# microcontroller.net
KiCad netlist of a schematic drawn in Altium Designer
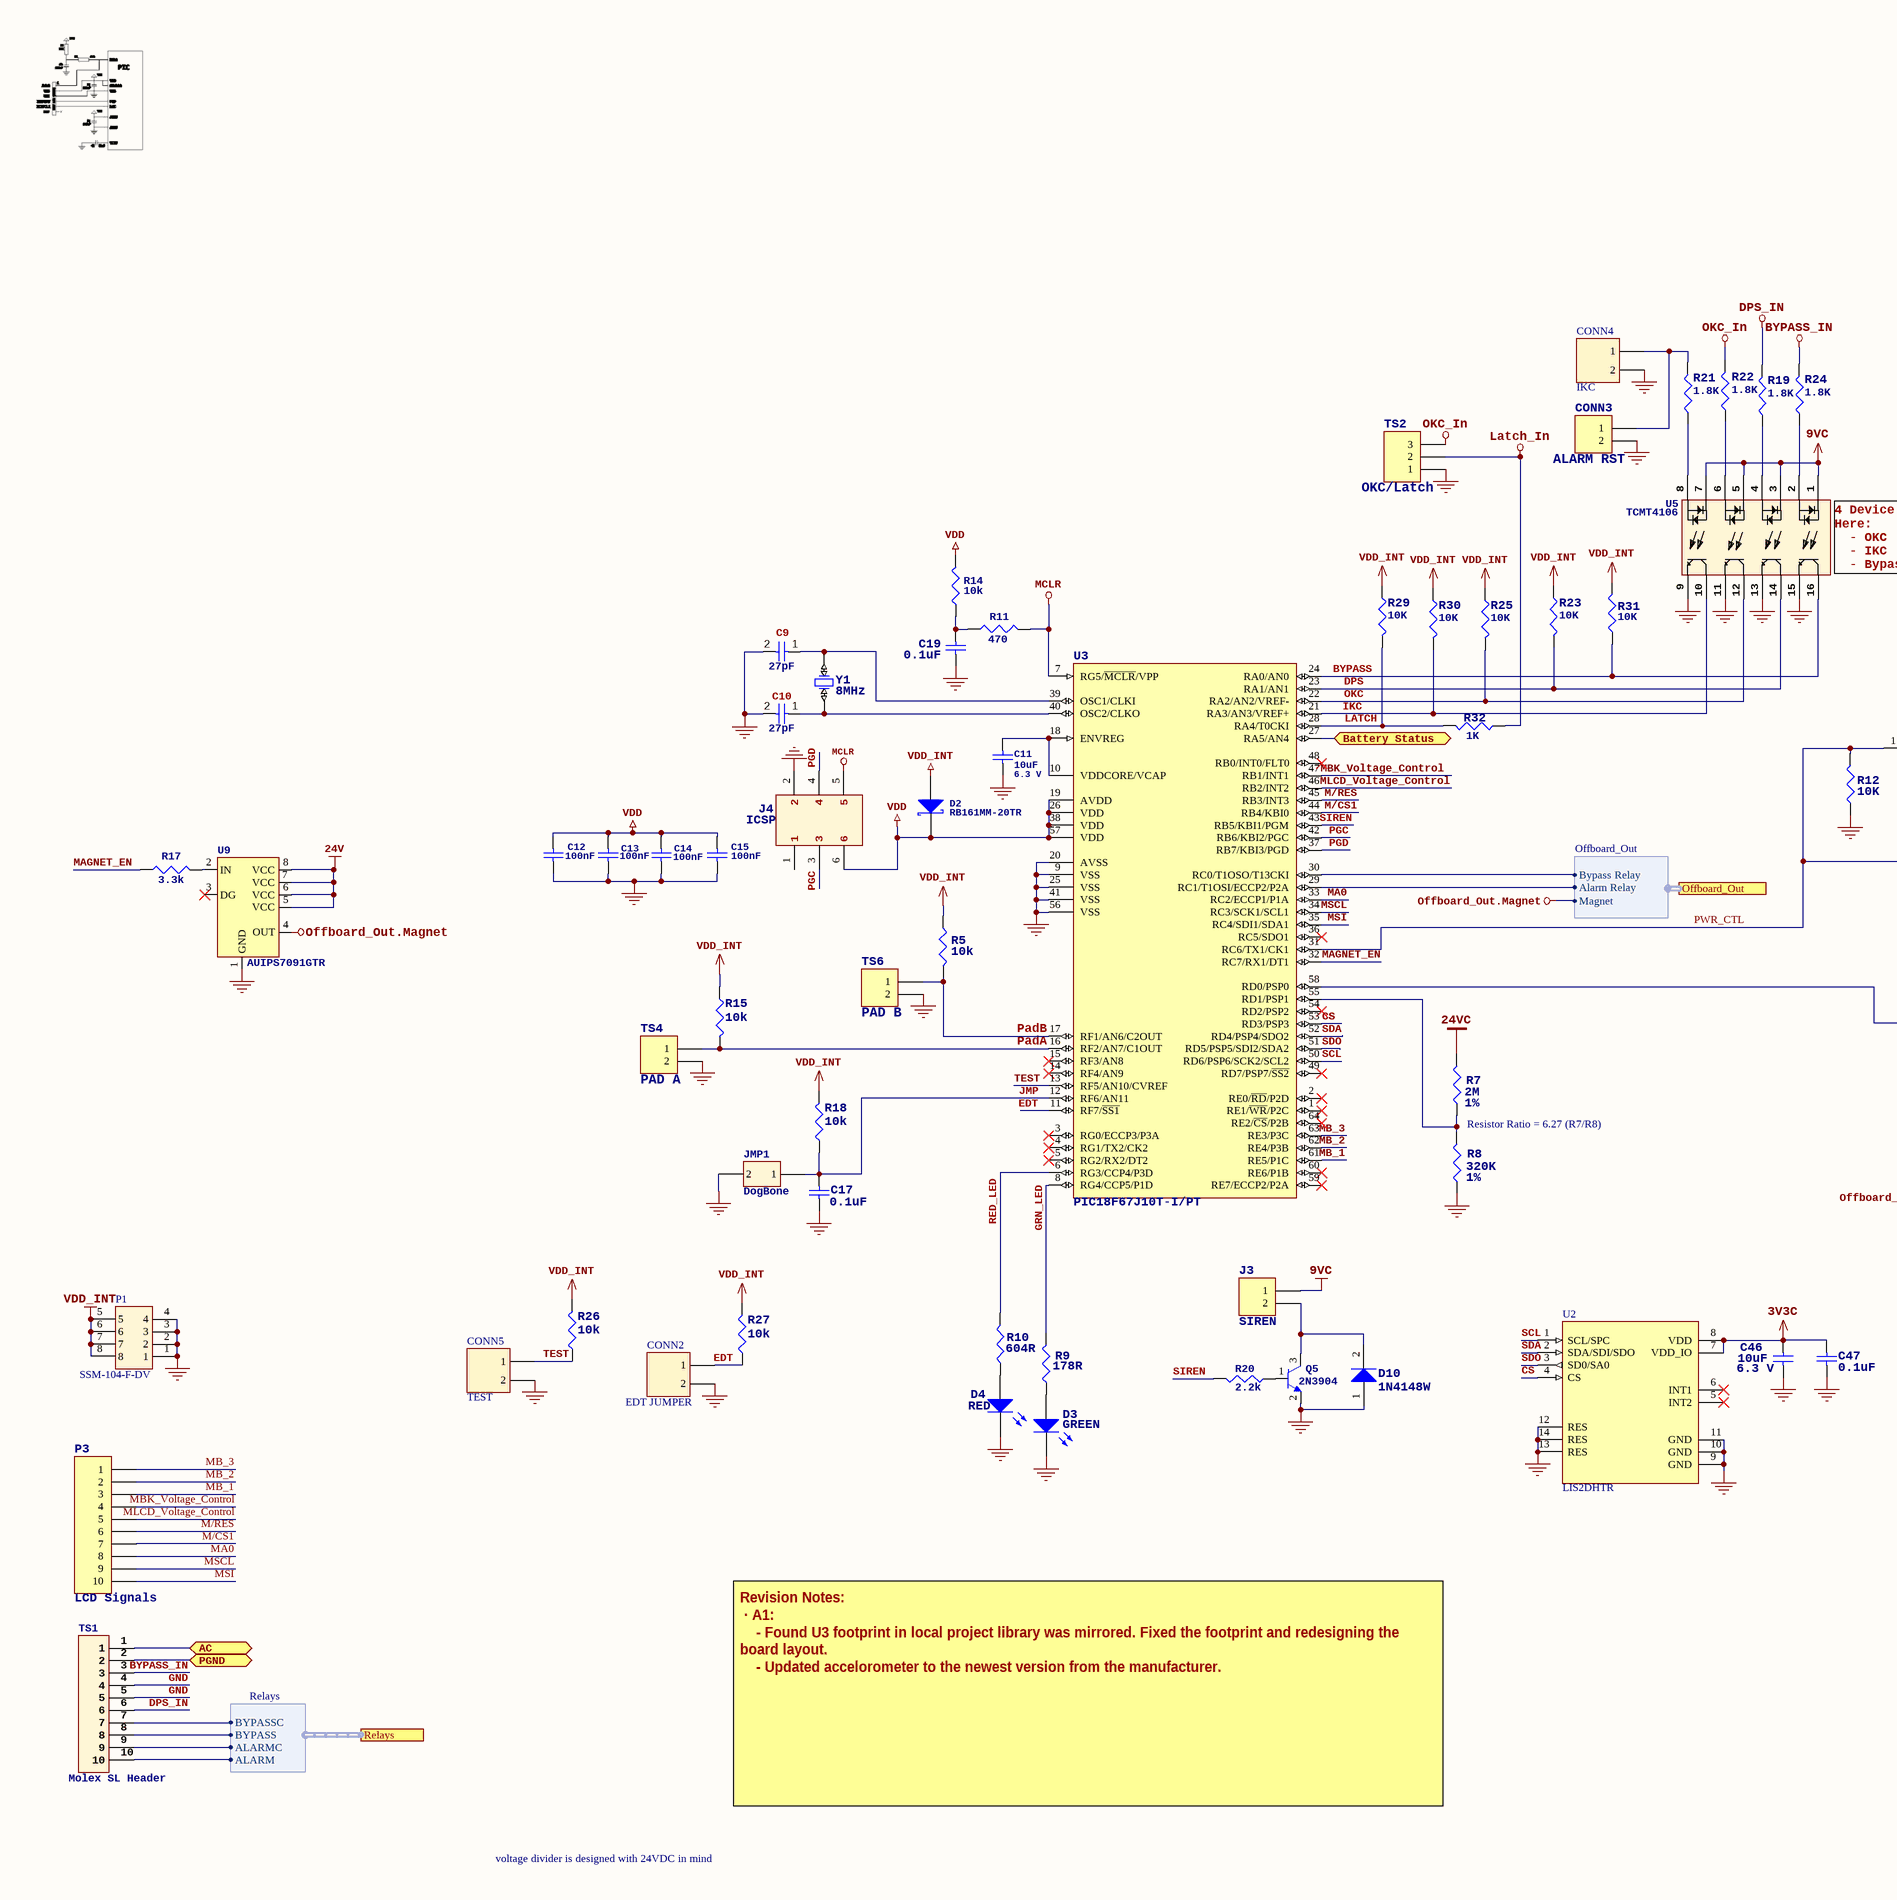
[diagram p0: microcontroller.SchDoc, left]
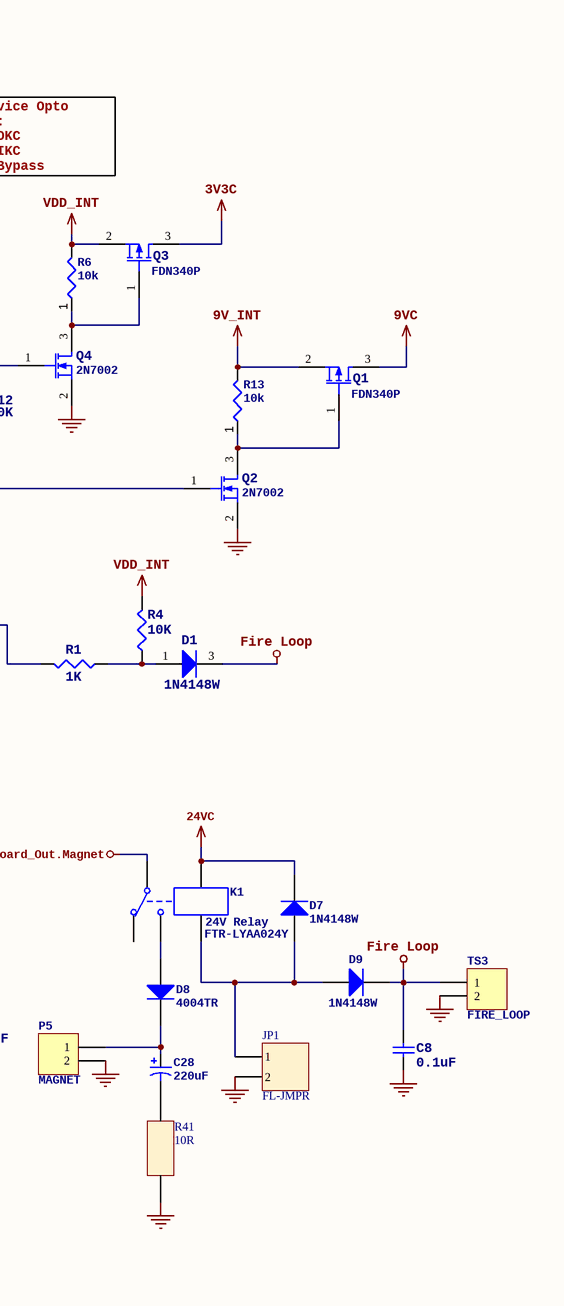
[diagram p1: microcontroller.SchDoc, right]

(export (version "E")
  (design (tool "Eeschema 10.0.6"))
  (components
    (comp (ref "C8")
      (value "0.1uF")
      (footprint "C0805")
      (description "Capacitor Ceramic X7R 50V 0.1uF 0805 SMT")
      (fields (field (name "MFR") "KEMET") (field (name "Comment") "Cap"))
      (libsource (lib "Miscellaneous Devices") (part "Cap"))
    )
    (comp (ref "C9")
      (value "27pF")
      (footprint "C0805")
      (description "Multilayer Ceramic Capacitors MLCC - SMD/SMT 100V 27pF C0G 0805 5% AEC-Q200")
      (fields (field (name "TOLERANCE") "20%") (field (name "MFR") "AVX"))
      (libsource (lib "Altium Concord Pro on Altium 365") (part "CAP-NP-2"))
    )
    (comp (ref "C10")
      (value "27pF")
      (footprint "C0805")
      (description "Multilayer Ceramic Capacitors MLCC - SMD/SMT 100V 27pF C0G 0805 5% AEC-Q200")
      (fields (field (name "TOLERANCE") "20%") (field (name "MFR") "AVX"))
      (libsource (lib "Altium Concord Pro on Altium 365") (part "CAP-NP-2"))
    )
    (comp (ref "C11")
      (value "10uF")
      (footprint "C0805")
      (description "Multilayer Ceramic Capacitors MLCC - SMD/SMT CGA 0805 6.3V 10uF X7R 10% AEC-Q200")
      (fields (field (name "MFR") "TDK") (field (name "VOLTAGE") "6.3 V") (field (name "Comment") "Cap"))
      (libsource (lib "Miscellaneous Devices") (part "Cap"))
    )
    (comp (ref "C12")
      (value "100nF")
      (footprint "C0805")
      (description "Capacitor")
      (fields (field (name "Comment") "Cap"))
      (libsource (lib "Miscellaneous Devices") (part "Cap"))
    )
    (comp (ref "C13")
      (value "100nF")
      (footprint "C0805")
      (description "Capacitor")
      (fields (field (name "Comment") "Cap"))
      (libsource (lib "Miscellaneous Devices") (part "Cap"))
    )
    (comp (ref "C14")
      (value "100nF")
      (footprint "C0805")
      (description "Capacitor")
      (fields (field (name "Comment") "Cap"))
      (libsource (lib "Miscellaneous Devices") (part "Cap"))
    )
    (comp (ref "C15")
      (value "100nF")
      (footprint "C0805")
      (description "Capacitor")
      (fields (field (name "Comment") "Cap"))
      (libsource (lib "Miscellaneous Devices") (part "Cap"))
    )
    (comp (ref "C17")
      (value "0.1uF")
      (footprint "C0805")
      (description "Capacitor Ceramic X7R 50V 0.1uF 0805 SMT")
      (fields (field (name "MFR") "KEMET") (field (name "Comment") "Cap"))
      (libsource (lib "Miscellaneous Devices") (part "Cap"))
    )
    (comp (ref "C19")
      (value "0.1uF")
      (footprint "C0805")
      (description "Capacitor Ceramic X7R 50V 0.1uF 0805 SMT")
      (fields (field (name "MFR") "KEMET") (field (name "Comment") "Cap"))
      (libsource (lib "Miscellaneous Devices") (part "Cap"))
    )
    (comp (ref "C28")
      (value "220uF")
      (footprint "10x12.5 CAP")
      (description "Polarized Capacitor (Surface Mount)")
      (fields (field (name "MFR") "Nichicon") (field (name "Comment") "Cap Pol3"))
      (libsource (lib "Miscellaneous Devices") (part "Cap Pol3"))
    )
    (comp (ref "C46")
      (value "10uF")
      (footprint "C0805")
      (description "Multilayer Ceramic Capacitors MLCC - SMD/SMT CGA 0805 6.3V 10uF X7R 10% AEC-Q200")
      (fields (field (name "MFR") "TDK") (field (name "VOLTAGE") "6.3 V") (field (name "Comment") "Cap"))
      (libsource (lib "Miscellaneous Devices") (part "Cap"))
    )
    (comp (ref "C47")
      (value "0.1uF")
      (footprint "C0805")
      (description "Capacitor Ceramic X7R 50V 0.1uF 0805 SMT")
      (fields (field (name "MFR") "KEMET") (field (name "Comment") "Cap"))
      (libsource (lib "Miscellaneous Devices") (part "Cap"))
    )
    (comp (ref "CONN2")
      (value "EDT JUMPER")
      (footprint "2 Pin Header")
      (description "2.54mm Pitch 2 Way 1 Row Straight Pin Header, Through Hole")
      (fields (field (name "MFR") "TE Connectivity"))
      (libsource (lib "Custom Components") (part "Header 2"))
    )
    (comp (ref "CONN3")
      (value "ALARM RST")
      (footprint "BAT-2")
      (description "Header, 2-Pin")
      (libsource (lib "Miscellaneous Connectors") (part "Header 2"))
    )
    (comp (ref "CONN4")
      (value "IKC")
      (footprint "2 Pin Header")
      (description "2.54mm Pitch 2 Way 1 Row Straight Pin Header, Through Hole")
      (fields (field (name "MFR") "TE Connectivity"))
      (libsource (lib "Custom Components") (part "Header 2"))
    )
    (comp (ref "CONN5")
      (value "TEST")
      (footprint "2 Pin Header")
      (description "2.54mm Pitch 2 Way 1 Row Straight Pin Header, Through Hole")
      (fields (field (name "MFR") "TE Connectivity"))
      (libsource (lib "Custom Components") (part "Header 2"))
    )
    (comp (ref "D1")
      (value "Diode")
      (footprint "SOT-23_M")
      (description "DIODE SIGNAL SMT 75 VOLTS")
      (fields (field (name "MFR P/N") "1N4148W"))
      (libsource (lib "") (part "Diode_2"))
    )
    (comp (ref "D2")
      (value "D Schottky")
      (footprint "SOD-123FL")
      (description "Schottky Barrier Rectifier")
      (fields (field (name "MFR") "ROHM Semiconductor") (field (name "MFR P/N") "RB161MM-20TR"))
      (libsource (lib "Custom Components") (part "D Schottky"))
    )
    (comp (ref "D3")
      (value "GREEN")
      (footprint "T-1 3/4")
      (description "Typical RED, GREEN, YELLOW, AMBER GaAs LED")
      (fields (field (name "MFR") "Kingbright"))
      (libsource (lib "Miscellaneous Devices") (part "LED2"))
    )
    (comp (ref "D4")
      (value "RED")
      (footprint "T-1 3/4")
      (description "Typical RED, GREEN, YELLOW, AMBER GaAs LED")
      (fields (field (name "MFR") "Kingbright"))
      (libsource (lib "Miscellaneous Devices") (part "LED2"))
    )
    (comp (ref "D7")
      (value "Diode")
      (footprint "SOT-23_M")
      (description "DIODE SIGNAL SMT 75 VOLTS")
      (fields (field (name "MFR P/N") "1N4148W"))
      (libsource (lib "Miscellaneous Devices") (part "Diode"))
    )
    (comp (ref "D8")
      (value "Diode")
      (footprint "SMB")
      (description "DIODE RECTIFIER 4004 SMT")
      (fields (field (name "MFR P/N") "4004TR"))
      (libsource (lib "Miscellaneous Devices") (part "Diode"))
    )
    (comp (ref "D9")
      (value "Diode")
      (footprint "SOT-23_M")
      (description "DIODE SIGNAL SMT 75 VOLTS")
      (fields (field (name "MFR P/N") "1N4148W"))
      (libsource (lib "") (part "Diode_3"))
    )
    (comp (ref "D10")
      (value "Diode")
      (footprint "SOT-23_M")
      (description "DIODE SIGNAL SMT 75 VOLTS")
      (fields (field (name "MFR P/N") "1N4148W"))
      (libsource (lib "") (part "Diode_1"))
    )
    (comp (ref "J3")
      (value "SIREN")
      (footprint "BAT-2")
      (description "Header, 2-Pin")
      (libsource (lib "Miscellaneous Connectors") (part "Header 2"))
    )
    (comp (ref "J4")
      (value "ICSP")
      (footprint "ICSP SMT")
      (description "ICSP Header, 6-Pin, 2 Row")
      (libsource (lib "Custom Components") (part "ICSP_PIC"))
    )
    (comp (ref "JMP1")
      (value "DogBone")
      (footprint "DogBone")
      (libsource (lib "Custom Components") (part "DogBone"))
    )
    (comp (ref "JP1")
      (value "FL-JMPR")
      (footprint "2 Pin Header")
      (description "2.54mm Pitch 2 Way 1 Row Straight Pin Header, Through Hole")
      (fields (field (name "MFR") "TE Connectivity"))
      (libsource (lib "") (part "Header 2_1"))
    )
    (comp (ref "K1")
      (value "24V Relay")
      (footprint "FTR-LY")
      (description "SPST (1 Form A)")
      (fields (field (name "MFR") "Fujitsu") (field (name "MFR P/N") "FTR-LYAA024Y"))
      (libsource (lib "Miscellaneous Devices") (part "Relay-SPDT"))
    )
    (comp (ref "P1")
      (value "LCD Power")
      (footprint "MOLEX 15453508")
      (fields (field (name "MFR") "Samtec") (field (name "MFR P/N") "SSM-104-F-DV"))
      (libsource (lib "Custom Components") (part "2x4 Header"))
    )
    (comp (ref "P3")
      (value "LCD Signals")
      (footprint "10 pin Header")
      (description "Headers & Wire Housings 10 PIN SIL VERTICAL SOCKET")
      (fields (field (name "MFR") "Harwin"))
      (libsource (lib "Custom Components") (part "Header 10"))
    )
    (comp (ref "P5")
      (value "MAGNET")
      (footprint "7025")
      (description "Header, 2-Pin")
      (fields (field (name "MFR") "Molex"))
      (libsource (lib "Miscellaneous Connectors") (part "Header 2"))
    )
    (comp (ref "Q1")
      (value "FDN340P")
      (footprint "SOT-23_N")
      (description "P-Channel MOSFET")
      (fields (field (name "MFR") "ON Semiconductor / Fairchild"))
      (libsource (lib "Miscellaneous Devices") (part "MOSFET-P"))
    )
    (comp (ref "Q2")
      (value "2N7002")
      (footprint "SOT-23_N")
      (description "N-Channel MOSFET")
      (fields (field (name "MFR") "ON Semiconductor"))
      (libsource (lib "Miscellaneous Devices") (part "MOSFET-N"))
    )
    (comp (ref "Q3")
      (value "FDN340P")
      (footprint "SOT-23_N")
      (description "P-Channel MOSFET")
      (fields (field (name "MFR") "ON Semiconductor / Fairchild"))
      (libsource (lib "Miscellaneous Devices") (part "MOSFET-P"))
    )
    (comp (ref "Q4")
      (value "2N7002")
      (footprint "SOT-23_N")
      (description "N-Channel MOSFET")
      (fields (field (name "MFR") "ON Semiconductor"))
      (libsource (lib "Miscellaneous Devices") (part "MOSFET-N"))
    )
    (comp (ref "Q5")
      (value "2N3904")
      (footprint "SOT-23_N")
      (description "NPN Darlington Bipolar Transistor")
      (libsource (lib "Miscellaneous Devices") (part "2N3904_SMT"))
    )
    (comp (ref "R1")
      (value "1K")
      (footprint "6-0805_N")
      (description "Resistor 1K Ohm 1% 0805 SMT")
      (fields (field (name "MFR") "Vishay/Dale") (field (name "Comment") "Res3"))
      (libsource (lib "Miscellaneous Devices") (part "Res3"))
    )
    (comp (ref "R4")
      (value "10K")
      (footprint "6-0805_N")
      (description "Resistor")
      (fields (field (name "Comment") "Res3"))
      (libsource (lib "Miscellaneous Devices") (part "Res3"))
    )
    (comp (ref "R5")
      (value "10k")
      (footprint "6-0805_N")
      (description "Resistor")
      (fields (field (name "Comment") "Res3"))
      (libsource (lib "Miscellaneous Devices") (part "Res3"))
    )
    (comp (ref "R6")
      (value "10k")
      (footprint "6-0805_N")
      (description "Chip Resistor, 10 KOhm, +/- 1%, 01 W, -55 to 155 degC, 0805")
      (fields (field (name "TOLERANCE") "1%") (field (name "POWER") "100mW"))
      (libsource (lib "Altium Concord Pro on Altium 365") (part "RES-2"))
    )
    (comp (ref "R7")
      (value "1%")
      (footprint "6-0805_N")
      (description "Resistor 2M Ohm 1% 0805 SMT")
      (fields (field (name "ALTIUM_VALUE") "2M") (field (name "MFR") "Vishay/Dale"))
      (libsource (lib "Miscellaneous Devices") (part "Res3"))
    )
    (comp (ref "R8")
      (value "1%")
      (footprint "6-0805_N")
      (description "Thin Film Resistors - SMD 1/8W 316K ohm 1% 50ppm")
      (fields (field (name "ALTIUM_VALUE") "320K") (field (name "MFR") "Yageo"))
      (libsource (lib "Miscellaneous Devices") (part "Res3"))
    )
    (comp (ref "R9")
      (value "178R")
      (footprint "6-0805_N")
      (description "Resistor")
      (fields (field (name "MFR") "Vishay / Dale") (field (name "Comment") "Res3"))
      (libsource (lib "Miscellaneous Devices") (part "Res3"))
    )
    (comp (ref "R10")
      (value "604R")
      (footprint "6-0805_N")
      (description "Thick Film Resistors - SMD 1/8Watt 604ohms 1%")
      (fields (field (name "MFR") "Vishay / Dale") (field (name "Comment") "Res3"))
      (libsource (lib "Miscellaneous Devices") (part "Res3"))
    )
    (comp (ref "R11")
      (value "470")
      (footprint "6-0805_N")
      (description "Chip Resistor, 1 KOhm, +/-1%, 0.1 W, -55 to 155 degC, 0603 (1608 Metric)")
      (fields (field (name "POWER") "100mW") (field (name "TOLERANCE") "1%"))
      (libsource (lib "") (part "RES-2_1"))
    )
    (comp (ref "R12")
      (value "10K")
      (footprint "6-0805_N")
      (description "Resistor")
      (fields (field (name "Comment") "Res3"))
      (libsource (lib "Miscellaneous Devices") (part "Res3"))
    )
    (comp (ref "R13")
      (value "10k")
      (footprint "6-0805_N")
      (description "Chip Resistor, 10 KOhm, +/- 1%, 01 W, -55 to 155 degC, 0805")
      (fields (field (name "TOLERANCE") "1%") (field (name "POWER") "100mW"))
      (libsource (lib "Altium Concord Pro on Altium 365") (part "RES-2"))
    )
    (comp (ref "R14")
      (value "10k")
      (footprint "6-0805_N")
      (description "Chip Resistor, 10 KOhm, +/- 1%, 01 W, -55 to 155 degC, 0805")
      (fields (field (name "TOLERANCE") "1%") (field (name "POWER") "100mW"))
      (libsource (lib "") (part "RES-2_1"))
    )
    (comp (ref "R15")
      (value "10k")
      (footprint "6-0805_N")
      (description "Resistor")
      (fields (field (name "Comment") "Res3"))
      (libsource (lib "Miscellaneous Devices") (part "Res3"))
    )
    (comp (ref "R17")
      (value "3.3k")
      (footprint "6-0805_N")
      (description "Resistor 3.3KOhm 5% 0805 SMT")
      (fields (field (name "MFR") "Vishay/Dale") (field (name "Comment") "Res3"))
      (libsource (lib "Miscellaneous Devices") (part "Res3"))
    )
    (comp (ref "R18")
      (value "10k")
      (footprint "6-0805_N")
      (description "Resistor")
      (fields (field (name "Comment") "Res3"))
      (libsource (lib "Miscellaneous Devices") (part "Res3"))
    )
    (comp (ref "R19")
      (value "1.8K")
      (footprint "6-0805_N")
      (description "Resistor")
      (fields (field (name "MFR") "Vishay / Dale") (field (name "Comment") "Res3"))
      (libsource (lib "Miscellaneous Devices") (part "Res3"))
    )
    (comp (ref "R20")
      (value "2.2k")
      (footprint "6-0805_N")
      (description "Chip Resistor, 2.2KOhm, +/- 5%, 01 W, -55 to 155 degC, 0805")
      (fields (field (name "TOLERANCE") "1%") (field (name "POWER") "100mW"))
      (libsource (lib "") (part "RES-2_1"))
    )
    (comp (ref "R21")
      (value "1.8K")
      (footprint "6-0805_N")
      (description "Resistor")
      (fields (field (name "MFR") "Vishay / Dale") (field (name "Comment") "Res3"))
      (libsource (lib "Miscellaneous Devices") (part "Res3"))
    )
    (comp (ref "R22")
      (value "1.8K")
      (footprint "6-0805_N")
      (description "Resistor")
      (fields (field (name "MFR") "Vishay / Dale") (field (name "Comment") "Res3"))
      (libsource (lib "Miscellaneous Devices") (part "Res3"))
    )
    (comp (ref "R23")
      (value "10K")
      (footprint "6-0805_N")
      (description "Resistor")
      (fields (field (name "Comment") "Res3"))
      (libsource (lib "Miscellaneous Devices") (part "Res3"))
    )
    (comp (ref "R24")
      (value "1.8K")
      (footprint "6-0805_N")
      (description "Resistor")
      (fields (field (name "MFR") "Vishay / Dale") (field (name "Comment") "Res3"))
      (libsource (lib "Miscellaneous Devices") (part "Res3"))
    )
    (comp (ref "R25")
      (value "10K")
      (footprint "6-0805_N")
      (description "Resistor")
      (fields (field (name "Comment") "Res3"))
      (libsource (lib "Miscellaneous Devices") (part "Res3"))
    )
    (comp (ref "R26")
      (value "10k")
      (footprint "6-0805_N")
      (description "Resistor")
      (fields (field (name "Comment") "Res3"))
      (libsource (lib "Miscellaneous Devices") (part "Res3"))
    )
    (comp (ref "R27")
      (value "10k")
      (footprint "6-0805_N")
      (description "Resistor")
      (fields (field (name "Comment") "Res3"))
      (libsource (lib "Miscellaneous Devices") (part "Res3"))
    )
    (comp (ref "R29")
      (value "10K")
      (footprint "6-0805_N")
      (description "Resistor")
      (fields (field (name "Comment") "Res3"))
      (libsource (lib "Miscellaneous Devices") (part "Res3"))
    )
    (comp (ref "R30")
      (value "10K")
      (footprint "6-0805_N")
      (description "Resistor")
      (fields (field (name "Comment") "Res3"))
      (libsource (lib "Miscellaneous Devices") (part "Res3"))
    )
    (comp (ref "R31")
      (value "10K")
      (footprint "6-0805_N")
      (description "Resistor")
      (fields (field (name "Comment") "Res3"))
      (libsource (lib "Miscellaneous Devices") (part "Res3"))
    )
    (comp (ref "R32")
      (value "1K")
      (footprint "6-0805_N")
      (description "Resistor 1K Ohm 1% 0805 SMT")
      (fields (field (name "MFR") "Vishay/Dale") (field (name "Comment") "Res3"))
      (libsource (lib "Miscellaneous Devices") (part "Res3"))
    )
    (comp (ref "R41")
      (value "10R")
      (footprint "RESC_1210")
      (description "Resistor 10 Ohm 5% 1210 SMD")
      (fields (field (name "MFR") "Vishay/Dale"))
      (libsource (lib "Custom Components") (part "RESC_1210"))
    )
    (comp (ref "TS1")
      (value "Molex SL Header")
      (footprint "10 Pin Molex Horizontal - duplicate")
      (fields (field (name "MFR") "Molex"))
      (libsource (lib "Custom Components") (part "SPOX-10P"))
    )
    (comp (ref "TS2")
      (value "OKC/Latch")
      (footprint "3 Pin Footprint")
      (description "Header, 3-Pin, Right Angle")
      (fields (field (name "MFR") "Molex"))
      (libsource (lib "Miscellaneous Connectors") (part "Header 3H"))
    )
    (comp (ref "TS3")
      (value "FIRE_LOOP")
      (footprint "BAT-2")
      (description "Header, 2-Pin, Right Angle")
      (libsource (lib "") (part "Header 2H_1"))
    )
    (comp (ref "TS4")
      (value "PAD A")
      (footprint "BAT-2")
      (description "Header, 2-Pin, Right Angle")
      (libsource (lib "Miscellaneous Connectors") (part "Header 2H"))
    )
    (comp (ref "TS6")
      (value "PAD B")
      (footprint "BAT-2")
      (description "Header, 2-Pin")
      (fields (field (name "MFR") "Molex"))
      (libsource (lib "Miscellaneous Connectors") (part "Header 2"))
    )
    (comp (ref "U2")
      (value "LIS2DHTR")
      (footprint "PQFN35P200X200X100-14N")
      (description "Accelerometer X, Y, Z Axis Â±2g, 4g, 8g, 16g 0.5Hz ~ 672Hz 14-LGA _2x2_")
      (fields (field (name "MF") "STMicroelectronics"))
      (libsource (lib "Custom Components") (part "LIS2DHTR"))
    )
    (comp (ref "U3")
      (value "PIC18F67J10T-I/PT")
      (footprint "PIC18F67J10T-I/PT")
      (fields (field (name "MFR") "Microchip"))
      (libsource (lib "Custom Components") (part "CMP-0116-00693-1"))
    )
    (comp (ref "U5")
      (value "TCMT4106")
      (footprint "SSOP-16")
      (description "Transistor Output Optocouplers Phototransistor Out Quad CTR > 160-320%")
      (fields (field (name "MFR") "Vishay Semiconductors"))
      (libsource (lib "Custom Components") (part "ILQ615-4X009"))
    )
    (comp (ref "U9")
      (value "AUIPS7091GTR")
      (footprint "SOIC127P600X175-8N")
      (description "High Side MOSFET Switcher")
      (fields (field (name "MFR") "International Rectifier/Infineon"))
      (libsource (lib "Custom Components") (part "AUIPS7091GTR"))
    )
    (comp (ref "Y1")
      (value "8MHz")
      (footprint "ABM3")
      (description "Crystal Oscillator 8MHz")
      (fields (field (name "MFR") "Abracom"))
      (libsource (lib "Miscellaneous Devices") (part "XTAL"))
    )
  )
  (nets
    (net (code "3") (name "/AC") (class "Default")
      (node (ref "TS1") (pin "1") (pinfunction "1_1") (pintype "passive"))
    )
    (net (code "4") (name "/ALARM") (class "Default")
      (node (ref "TS1") (pin "10") (pinfunction "10_10") (pintype "passive"))
    )
    (net (code "5") (name "/ALARMC") (class "Default")
      (node (ref "TS1") (pin "9") (pinfunction "9_9") (pintype "passive"))
    )
    (net (code "6") (name "/Alarm Relay") (class "Default")
      (node (ref "U3") (pin "29") (pinfunction "RC1/T1OSI/ECCP2/P2A_29") (pintype "bidirectional"))
    )
    (net (code "7") (name "/BYPASS") (class "Default")
      (node (ref "R31") (pin "1") (pinfunction "1_1") (pintype "passive"))
      (node (ref "U3") (pin "24") (pinfunction "RA0/AN0_24") (pintype "bidirectional"))
      (node (ref "U5") (pin "16") (pinfunction "16_16") (pintype "passive"))
    )
    (net (code "8") (name "/BYPASSC") (class "Default")
      (node (ref "TS1") (pin "7") (pinfunction "7_7") (pintype "passive"))
    )
    (net (code "9") (name "/Battery Status") (class "Default")
      (node (ref "U3") (pin "27") (pinfunction "RA5/AN4_27") (pintype "bidirectional"))
    )
    (net (code "10") (name "/Bypass Relay") (class "Default")
      (node (ref "U3") (pin "30") (pinfunction "RC0/T1OSO/T13CKI_30") (pintype "bidirectional"))
    )
    (net (code "11") (name "/CS") (class "Default")
      (node (ref "U2") (pin "4") (pinfunction "CS_4") (pintype "input"))
      (node (ref "U3") (pin "53") (pinfunction "RD3/PSP3_53") (pintype "bidirectional"))
    )
    (net (code "12") (name "/DPS") (class "Default")
      (node (ref "R23") (pin "2") (pinfunction "2_2") (pintype "passive"))
      (node (ref "U3") (pin "23") (pinfunction "RA1/AN1_23") (pintype "bidirectional"))
      (node (ref "U5") (pin "14") (pinfunction "14_14") (pintype "passive"))
    )
    (net (code "13") (name "/EDT") (class "Default")
      (node (ref "CONN2") (pin "1") (pinfunction "1_1") (pintype "passive"))
      (node (ref "R27") (pin "1") (pinfunction "1_1") (pintype "passive"))
      (node (ref "U3") (pin "11") (pinfunction "RF7/~{SS1}_11") (pintype "bidirectional"))
    )
    (net (code "14") (name "/GRN_LED") (class "Default")
      (node (ref "R9") (pin "2") (pinfunction "2_2") (pintype "passive"))
      (node (ref "U3") (pin "8") (pinfunction "RG4/CCP5/P1D_8") (pintype "bidirectional"))
    )
    (net (code "15") (name "/IKC") (class "Default")
      (node (ref "R30") (pin "2") (pinfunction "2_2") (pintype "passive"))
      (node (ref "U3") (pin "21") (pinfunction "RA3/AN3/VREF+_21") (pintype "bidirectional"))
      (node (ref "U5") (pin "10") (pinfunction "10_10") (pintype "passive"))
    )
    (net (code "16") (name "/JMP") (class "Default")
      (node (ref "C17") (pin "1") (pinfunction "1_1") (pintype "passive"))
      (node (ref "JMP1") (pin "1") (pinfunction "1_1") (pintype "passive"))
      (node (ref "R18") (pin "1") (pinfunction "1_1") (pintype "passive"))
      (node (ref "U3") (pin "12") (pinfunction "RF6/AN11_12") (pintype "bidirectional"))
    )
    (net (code "17") (name "/LATCH") (class "Default")
      (node (ref "R29") (pin "2") (pinfunction "2_2") (pintype "passive"))
      (node (ref "R32") (pin "2") (pinfunction "2_2") (pintype "passive"))
      (node (ref "U3") (pin "28") (pinfunction "RA4/T0CKI_28") (pintype "bidirectional"))
    )
    (net (code "18") (name "/MA0") (class "Default")
      (node (ref "P3") (pin "8") (pinfunction "8_8") (pintype "passive"))
      (node (ref "U3") (pin "33") (pinfunction "RC2/ECCP1/P1A_33") (pintype "bidirectional"))
    )
    (net (code "19") (name "/MAGNET_EN") (class "Default")
      (node (ref "R17") (pin "1") (pinfunction "1_1") (pintype "passive"))
      (node (ref "U3") (pin "32") (pinfunction "RC7/RX1/DT1_32") (pintype "bidirectional"))
    )
    (net (code "20") (name "/MBK_Voltage_Control") (class "Default")
      (node (ref "P3") (pin "4") (pinfunction "4_4") (pintype "passive"))
      (node (ref "U3") (pin "47") (pinfunction "RB1/INT1_47") (pintype "bidirectional"))
    )
    (net (code "21") (name "/MB_1") (class "Default")
      (node (ref "P3") (pin "3") (pinfunction "3_3") (pintype "passive"))
      (node (ref "U3") (pin "61") (pinfunction "RE5/P1C_61") (pintype "bidirectional"))
    )
    (net (code "22") (name "/MB_2") (class "Default")
      (node (ref "P3") (pin "2") (pinfunction "2_2") (pintype "passive"))
      (node (ref "U3") (pin "62") (pinfunction "RE4/P3B_62") (pintype "bidirectional"))
    )
    (net (code "23") (name "/MB_3") (class "Default")
      (node (ref "P3") (pin "1") (pinfunction "1_1") (pintype "passive"))
      (node (ref "U3") (pin "63") (pinfunction "RE3/P3C_63") (pintype "bidirectional"))
    )
    (net (code "24") (name "/MLCD_Voltage_Control") (class "Default")
      (node (ref "P3") (pin "5") (pinfunction "5_5") (pintype "passive"))
      (node (ref "U3") (pin "46") (pinfunction "RB2/INT2_46") (pintype "bidirectional"))
    )
    (net (code "25") (name "/MSCL") (class "Default")
      (node (ref "P3") (pin "9") (pinfunction "9_9") (pintype "passive"))
      (node (ref "U3") (pin "34") (pinfunction "RC3/SCK1/SCL1_34") (pintype "bidirectional"))
    )
    (net (code "26") (name "/MSI") (class "Default")
      (node (ref "P3") (pin "10") (pinfunction "10_10") (pintype "passive"))
      (node (ref "U3") (pin "35") (pinfunction "RC4/SDI1/SDA1_35") (pintype "bidirectional"))
    )
    (net (code "27") (name "/M{slash}CS1") (class "Default")
      (node (ref "P3") (pin "7") (pinfunction "7_7") (pintype "passive"))
      (node (ref "U3") (pin "44") (pinfunction "RB4/KBI0_44") (pintype "bidirectional"))
    )
    (net (code "28") (name "/M{slash}RES") (class "Default")
      (node (ref "P3") (pin "6") (pinfunction "6_6") (pintype "passive"))
      (node (ref "U3") (pin "45") (pinfunction "RB3/INT3_45") (pintype "bidirectional"))
    )
    (net (code "29") (name "/OKC") (class "Default")
      (node (ref "R25") (pin "2") (pinfunction "2_2") (pintype "passive"))
      (node (ref "U3") (pin "22") (pinfunction "RA2/AN2/VREF-_22") (pintype "bidirectional"))
      (node (ref "U5") (pin "12") (pinfunction "12_12") (pintype "passive"))
    )
    (net (code "30") (name "/PGC") (class "Default")
      (node (ref "J4") (pin "3") (pinfunction "3_3") (pintype "passive"))
      (node (ref "U3") (pin "42") (pinfunction "RB6/KBI2/PGC_42") (pintype "bidirectional"))
    )
    (net (code "31") (name "/PGD") (class "Default")
      (node (ref "J4") (pin "4") (pinfunction "4_4") (pintype "passive"))
      (node (ref "U3") (pin "37") (pinfunction "RB7/KBI3/PGD_37") (pintype "bidirectional"))
    )
    (net (code "32") (name "/PGND") (class "Default")
      (node (ref "TS1") (pin "2") (pinfunction "2_2") (pintype "passive"))
    )
    (net (code "33") (name "/PWR_CTL") (class "Default")
      (node (ref "Q2") (pin "1") (pinfunction "G_1") (pintype "passive"))
      (node (ref "Q4") (pin "1") (pinfunction "G_1") (pintype "passive"))
      (node (ref "R12") (pin "2") (pinfunction "2_2") (pintype "passive"))
      (node (ref "U3") (pin "31") (pinfunction "RC6/TX1/CK1_31") (pintype "bidirectional"))
    )
    (net (code "34") (name "/PadA") (class "Default")
      (node (ref "R15") (pin "2") (pinfunction "2_2") (pintype "passive"))
      (node (ref "TS4") (pin "1") (pinfunction "1_1") (pintype "passive"))
      (node (ref "U3") (pin "16") (pinfunction "RF2/AN7/C1OUT_16") (pintype "bidirectional"))
    )
    (net (code "35") (name "/PadB") (class "Default")
      (node (ref "R5") (pin "2") (pinfunction "2_2") (pintype "passive"))
      (node (ref "TS6") (pin "1") (pinfunction "1_1") (pintype "passive"))
      (node (ref "U3") (pin "17") (pinfunction "RF1/AN6/C2OUT_17") (pintype "bidirectional"))
    )
    (net (code "36") (name "/RED_LED") (class "Default")
      (node (ref "R10") (pin "2") (pinfunction "2_2") (pintype "passive"))
      (node (ref "U3") (pin "6") (pinfunction "RG3/CCP4/P3D_6") (pintype "bidirectional"))
    )
    (net (code "37") (name "/SCL") (class "Default")
      (node (ref "U2") (pin "1") (pinfunction "SCL/SPC_1") (pintype "input"))
      (node (ref "U3") (pin "50") (pinfunction "RD6/PSP6/SCK2/SCL2_50") (pintype "bidirectional"))
    )
    (net (code "38") (name "/SDA") (class "Default")
      (node (ref "U2") (pin "2") (pinfunction "SDA/SDI/SDO_2") (pintype "input"))
      (node (ref "U3") (pin "52") (pinfunction "RD4/PSP4/SDO2_52") (pintype "bidirectional"))
    )
    (net (code "39") (name "/SDO") (class "Default")
      (node (ref "U2") (pin "3") (pinfunction "SD0/SA0_3") (pintype "output"))
      (node (ref "U3") (pin "51") (pinfunction "RD5/PSP5/SDI2/SDA2_51") (pintype "bidirectional"))
    )
    (net (code "40") (name "/SIREN") (class "Default")
      (node (ref "R20") (pin "2") (pinfunction "2_2") (pintype "passive"))
      (node (ref "U3") (pin "43") (pinfunction "RB5/KBI1/PGM_43") (pintype "bidirectional"))
    )
    (net (code "41") (name "/TEST") (class "Default")
      (node (ref "CONN5") (pin "1") (pinfunction "1_1") (pintype "passive"))
      (node (ref "R26") (pin "1") (pinfunction "1_1") (pintype "passive"))
      (node (ref "U3") (pin "13") (pinfunction "RF5/AN10/CVREF_13") (pintype "bidirectional"))
    )
    (net (code "44") (name "3V3C") (class "Default")
      (node (ref "C46") (pin "1") (pinfunction "1_1") (pintype "passive"))
      (node (ref "C47") (pin "1") (pinfunction "1_1") (pintype "passive"))
      (node (ref "Q3") (pin "3") (pinfunction "D_3") (pintype "passive"))
      (node (ref "U2") (pin "7") (pinfunction "VDD_IO_7") (pintype "power_in"))
      (node (ref "U2") (pin "8") (pinfunction "VDD_8") (pintype "power_in"))
    )
    (net (code "45") (name "9VC") (class "Default")
      (node (ref "J3") (pin "1") (pinfunction "1_1") (pintype "passive"))
      (node (ref "Q1") (pin "3") (pinfunction "D_3") (pintype "passive"))
      (node (ref "U5") (pin "1") (pinfunction "1_1") (pintype "passive"))
      (node (ref "U5") (pin "3") (pinfunction "3_3") (pintype "passive"))
      (node (ref "U5") (pin "5") (pinfunction "5_5") (pintype "passive"))
      (node (ref "U5") (pin "7") (pinfunction "7_7") (pintype "passive"))
    )
    (net (code "46") (name "9V_INT") (class "Default")
      (node (ref "Q1") (pin "2") (pinfunction "S_2") (pintype "passive"))
      (node (ref "R13") (pin "2") (pinfunction "2_2") (pintype "passive"))
    )
    (net (code "47") (name "24V") (class "Default")
      (node (ref "U9") (pin "5") (pinfunction "VCC_5") (pintype "power_in"))
      (node (ref "U9") (pin "6") (pinfunction "VCC_6") (pintype "power_in"))
      (node (ref "U9") (pin "7") (pinfunction "VCC_7") (pintype "power_in"))
      (node (ref "U9") (pin "8") (pinfunction "VCC_8") (pintype "power_in"))
    )
    (net (code "48") (name "24VC") (class "Default")
      (node (ref "D7") (pin "2") (pinfunction "K_2") (pintype "passive"))
      (node (ref "K1") (pin "4") (pinfunction "4_4") (pintype "passive"))
      (node (ref "R7") (pin "2") (pinfunction "2_2") (pintype "passive"))
    )
    (net (code "49") (name "BYPASS_IN") (class "Default")
      (node (ref "R24") (pin "2") (pinfunction "2_2") (pintype "passive"))
      (node (ref "TS1") (pin "3") (pinfunction "3_3") (pintype "passive"))
    )
    (net (code "50") (name "DPS_IN") (class "Default")
      (node (ref "R19") (pin "2") (pinfunction "2_2") (pintype "passive"))
      (node (ref "TS1") (pin "6") (pinfunction "6_6") (pintype "passive"))
    )
    (net (code "51") (name "Fire Loop") (class "Default")
      (node (ref "C8") (pin "1") (pinfunction "1_1") (pintype "passive"))
      (node (ref "D1") (pin "3") (pinfunction "3_3") (pintype "passive"))
      (node (ref "D9") (pin "2") (pinfunction "2_2") (pintype "passive"))
      (node (ref "TS3") (pin "1") (pinfunction "1_1") (pintype "passive"))
    )
    (net (code "52") (name "GND") (class "Default")
      (node (ref "C10") (pin "2") (pinfunction "2_2") (pintype "passive"))
      (node (ref "C11") (pin "2") (pinfunction "2_2") (pintype "passive"))
      (node (ref "C12") (pin "2") (pinfunction "2_2") (pintype "passive"))
      (node (ref "C13") (pin "2") (pinfunction "2_2") (pintype "passive"))
      (node (ref "C14") (pin "1") (pinfunction "1_1") (pintype "passive"))
      (node (ref "C15") (pin "2") (pinfunction "2_2") (pintype "passive"))
      (node (ref "C17") (pin "2") (pinfunction "2_2") (pintype "passive"))
      (node (ref "C19") (pin "2") (pinfunction "2_2") (pintype "passive"))
      (node (ref "C46") (pin "2") (pinfunction "2_2") (pintype "passive"))
      (node (ref "C47") (pin "2") (pinfunction "2_2") (pintype "passive"))
      (node (ref "C8") (pin "2") (pinfunction "2_2") (pintype "passive"))
      (node (ref "C9") (pin "2") (pinfunction "2_2") (pintype "passive"))
      (node (ref "CONN2") (pin "2") (pinfunction "2_2") (pintype "passive"))
      (node (ref "CONN3") (pin "2") (pinfunction "2_2") (pintype "passive"))
      (node (ref "CONN4") (pin "2") (pinfunction "2_2") (pintype "passive"))
      (node (ref "CONN5") (pin "2") (pinfunction "2_2") (pintype "passive"))
      (node (ref "D10") (pin "1") (pinfunction "1_1") (pintype "passive"))
      (node (ref "D3") (pin "2") (pinfunction "K_2") (pintype "passive"))
      (node (ref "D4") (pin "2") (pinfunction "K_2") (pintype "passive"))
      (node (ref "J4") (pin "2") (pinfunction "2_2") (pintype "passive"))
      (node (ref "JMP1") (pin "2") (pinfunction "2_2") (pintype "passive"))
      (node (ref "JP1") (pin "2") (pinfunction "2_2") (pintype "passive"))
      (node (ref "P1") (pin "1") (pinfunction "1_1") (pintype "passive"))
      (node (ref "P1") (pin "2") (pinfunction "2_2") (pintype "passive"))
      (node (ref "P1") (pin "3") (pinfunction "3_3") (pintype "passive"))
      (node (ref "P1") (pin "4") (pinfunction "4_4") (pintype "passive"))
      (node (ref "P5") (pin "2") (pinfunction "2_2") (pintype "passive"))
      (node (ref "Q2") (pin "2") (pinfunction "S_2") (pintype "passive"))
      (node (ref "Q4") (pin "2") (pinfunction "S_2") (pintype "passive"))
      (node (ref "Q5") (pin "2") (pinfunction "E_2") (pintype "passive"))
      (node (ref "R12") (pin "1") (pinfunction "1_1") (pintype "passive"))
      (node (ref "R41") (pin "2") (pinfunction "2_2") (pintype "passive"))
      (node (ref "R8") (pin "1") (pinfunction "1_1") (pintype "passive"))
      (node (ref "TS1") (pin "4") (pinfunction "4_4") (pintype "passive"))
      (node (ref "TS1") (pin "5") (pinfunction "5_5") (pintype "passive"))
      (node (ref "TS2") (pin "1") (pinfunction "1_1") (pintype "passive"))
      (node (ref "TS3") (pin "2") (pinfunction "2_2") (pintype "passive"))
      (node (ref "TS4") (pin "2") (pinfunction "2_2") (pintype "passive"))
      (node (ref "TS6") (pin "2") (pinfunction "2_2") (pintype "passive"))
      (node (ref "U2") (pin "10") (pinfunction "GND_10") (pintype "power_in"))
      (node (ref "U2") (pin "11") (pinfunction "GND_11") (pintype "passive"))
      (node (ref "U2") (pin "12") (pinfunction "RES_12") (pintype "passive"))
      (node (ref "U2") (pin "13") (pinfunction "RES_13") (pintype "passive"))
      (node (ref "U2") (pin "14") (pinfunction "RES_14") (pintype "passive"))
      (node (ref "U2") (pin "9") (pinfunction "GND_9") (pintype "power_in"))
      (node (ref "U3") (pin "20") (pinfunction "AVSS_20") (pintype "power_in"))
      (node (ref "U3") (pin "25") (pinfunction "VSS_25") (pintype "power_in"))
      (node (ref "U3") (pin "41") (pinfunction "VSS_41") (pintype "power_in"))
      (node (ref "U3") (pin "56") (pinfunction "VSS_56") (pintype "power_in"))
      (node (ref "U3") (pin "9") (pinfunction "VSS_9") (pintype "power_in"))
      (node (ref "U5") (pin "11") (pinfunction "11_11") (pintype "passive"))
      (node (ref "U5") (pin "13") (pinfunction "13_13") (pintype "passive"))
      (node (ref "U5") (pin "15") (pinfunction "15_15") (pintype "passive"))
      (node (ref "U5") (pin "9") (pinfunction "9_9") (pintype "passive"))
      (node (ref "U9") (pin "1") (pinfunction "GND_1") (pintype "power_in"))
    )
    (net (code "53") (name "Latch_In") (class "Default")
      (node (ref "R32") (pin "1") (pinfunction "1_1") (pintype "passive"))
      (node (ref "TS2") (pin "2") (pinfunction "2_2") (pintype "passive"))
    )
    (net (code "54") (name "MCLR") (class "Default")
      (node (ref "J4") (pin "5") (pinfunction "5_5") (pintype "passive"))
      (node (ref "R11") (pin "2") (pinfunction "2_2") (pintype "passive"))
      (node (ref "U3") (pin "7") (pinfunction "RG5/~{MCLR}/VPP_7") (pintype "input"))
    )
    (net (code "55") (name "Net-(C19-Pad1)") (class "Default")
      (node (ref "C19") (pin "1") (pinfunction "1_1") (pintype "passive"))
      (node (ref "R11") (pin "1") (pinfunction "1_1") (pintype "passive"))
      (node (ref "R14") (pin "1") (pinfunction "1_1") (pintype "passive"))
    )
    (net (code "56") (name "Net-(C28-Pad2)") (class "Default")
      (node (ref "C28") (pin "2") (pinfunction "2_2") (pintype "passive"))
      (node (ref "R41") (pin "1") (pinfunction "1_1") (pintype "passive"))
    )
    (net (code "57") (name "Net-(CONN3-Pad1)") (class "Default")
      (node (ref "CONN3") (pin "1") (pinfunction "1_1") (pintype "passive"))
      (node (ref "CONN4") (pin "1") (pinfunction "1_1") (pintype "passive"))
      (node (ref "R21") (pin "2") (pinfunction "2_2") (pintype "passive"))
    )
    (net (code "58") (name "Net-(D1-Pad1)") (class "Default")
      (node (ref "D1") (pin "1") (pinfunction "1_1") (pintype "passive"))
      (node (ref "R1") (pin "1") (pinfunction "1_1") (pintype "passive"))
      (node (ref "R4") (pin "1") (pinfunction "1_1") (pintype "passive"))
    )
    (net (code "59") (name "Net-(D3-A)") (class "Default")
      (node (ref "D3") (pin "1") (pinfunction "A_1") (pintype "passive"))
      (node (ref "R9") (pin "1") (pinfunction "1_1") (pintype "passive"))
    )
    (net (code "60") (name "Net-(D4-A)") (class "Default")
      (node (ref "D4") (pin "1") (pinfunction "A_1") (pintype "passive"))
      (node (ref "R10") (pin "1") (pinfunction "1_1") (pintype "passive"))
    )
    (net (code "61") (name "Net-(D7-A)") (class "Default")
      (node (ref "D7") (pin "1") (pinfunction "A_1") (pintype "passive"))
      (node (ref "D9") (pin "1") (pinfunction "1_1") (pintype "passive"))
      (node (ref "JP1") (pin "1") (pinfunction "1_1") (pintype "passive"))
      (node (ref "K1") (pin "5") (pinfunction "5_5") (pintype "passive"))
    )
    (net (code "62") (name "Net-(D8-A)") (class "Default")
      (node (ref "D8") (pin "1") (pinfunction "A_1") (pintype "passive"))
      (node (ref "K1") (pin "3") (pinfunction "3_3") (pintype "passive"))
    )
    (net (code "63") (name "Net-(D8-K)") (class "Default")
      (node (ref "C28") (pin "1") (pinfunction "1_1") (pintype "passive"))
      (node (ref "D8") (pin "2") (pinfunction "K_2") (pintype "passive"))
      (node (ref "P5") (pin "1") (pinfunction "1_1") (pintype "passive"))
    )
    (net (code "64") (name "Net-(Q1-G)") (class "Default")
      (node (ref "Q1") (pin "1") (pinfunction "G_1") (pintype "passive"))
      (node (ref "Q2") (pin "3") (pinfunction "D_3") (pintype "passive"))
      (node (ref "R13") (pin "1") (pinfunction "1_1") (pintype "passive"))
    )
    (net (code "65") (name "Net-(Q3-G)") (class "Default")
      (node (ref "Q3") (pin "1") (pinfunction "G_1") (pintype "passive"))
      (node (ref "Q4") (pin "3") (pinfunction "D_3") (pintype "passive"))
      (node (ref "R6") (pin "1") (pinfunction "1_1") (pintype "passive"))
    )
    (net (code "66") (name "Net-(Q5-B)") (class "Default")
      (node (ref "Q5") (pin "1") (pinfunction "B_1") (pintype "passive"))
      (node (ref "R20") (pin "1") (pinfunction "1_1") (pintype "passive"))
    )
    (net (code "67") (name "Net-(Q5-C)") (class "Default")
      (node (ref "D10") (pin "2") (pinfunction "2_2") (pintype "passive"))
      (node (ref "J3") (pin "2") (pinfunction "2_2") (pintype "passive"))
      (node (ref "Q5") (pin "3") (pinfunction "C_3") (pintype "passive"))
    )
    (net (code "68") (name "Net-(R19-Pad1)") (class "Default")
      (node (ref "R19") (pin "1") (pinfunction "1_1") (pintype "passive"))
      (node (ref "U5") (pin "4") (pinfunction "4_4") (pintype "passive"))
    )
    (net (code "69") (name "Net-(R21-Pad1)") (class "Default")
      (node (ref "R21") (pin "1") (pinfunction "1_1") (pintype "passive"))
      (node (ref "U5") (pin "8") (pinfunction "8_8") (pintype "passive"))
    )
    (net (code "70") (name "Net-(R22-Pad1)") (class "Default")
      (node (ref "R22") (pin "1") (pinfunction "1_1") (pintype "passive"))
      (node (ref "U5") (pin "6") (pinfunction "6_6") (pintype "passive"))
    )
    (net (code "71") (name "Net-(R24-Pad1)") (class "Default")
      (node (ref "R24") (pin "1") (pinfunction "1_1") (pintype "passive"))
      (node (ref "U5") (pin "2") (pinfunction "2_2") (pintype "passive"))
    )
    (net (code "72") (name "Net-(U3-ENVREG)") (class "Default")
      (node (ref "C11") (pin "1") (pinfunction "1_1") (pintype "passive"))
      (node (ref "U3") (pin "10") (pinfunction "VDDCORE/VCAP_10") (pintype "power_in"))
      (node (ref "U3") (pin "18") (pinfunction "ENVREG_18") (pintype "input"))
    )
    (net (code "73") (name "Net-(U3-OSC1{slash}CLKI)") (class "Default")
      (node (ref "C9") (pin "1") (pinfunction "1_1") (pintype "passive"))
      (node (ref "U3") (pin "39") (pinfunction "OSC1/CLKI_39") (pintype "bidirectional"))
      (node (ref "Y1") (pin "1") (pinfunction "OSC1_1") (pintype "bidirectional"))
    )
    (net (code "74") (name "Net-(U3-OSC2{slash}CLKO)") (class "Default")
      (node (ref "C10") (pin "1") (pinfunction "1_1") (pintype "passive"))
      (node (ref "U3") (pin "40") (pinfunction "OSC2/CLKO_40") (pintype "bidirectional"))
      (node (ref "Y1") (pin "2") (pinfunction "OSC2_2") (pintype "bidirectional"))
    )
    (net (code "75") (name "Net-(U3-RD0{slash}PSP0)") (class "Default")
      (node (ref "R1") (pin "2") (pinfunction "2_2") (pintype "passive"))
      (node (ref "U3") (pin "58") (pinfunction "RD0/PSP0_58") (pintype "bidirectional"))
    )
    (net (code "76") (name "Net-(U3-RD1{slash}PSP1)") (class "Default")
      (node (ref "R7") (pin "1") (pinfunction "1_1") (pintype "passive"))
      (node (ref "R8") (pin "2") (pinfunction "2_2") (pintype "passive"))
      (node (ref "U3") (pin "55") (pinfunction "RD1/PSP1_55") (pintype "bidirectional"))
    )
    (net (code "77") (name "Net-(U9-IN)") (class "Default")
      (node (ref "R17") (pin "2") (pinfunction "2_2") (pintype "passive"))
      (node (ref "U9") (pin "2") (pinfunction "IN_2") (pintype "passive"))
    )
    (net (code "78") (name "OKC_In") (class "Default")
      (node (ref "R22") (pin "2") (pinfunction "2_2") (pintype "passive"))
      (node (ref "TS2") (pin "3") (pinfunction "3_3") (pintype "passive"))
    )
    (net (code "79") (name "Offboard_Out.Magnet") (class "Default")
      (node (ref "K1") (pin "1") (pinfunction "1_1") (pintype "passive"))
      (node (ref "U9") (pin "4") (pinfunction "OUT_4") (pintype "passive"))
    )
    (net (code "80") (name "VDD") (class "Default")
      (node (ref "C12") (pin "1") (pinfunction "1_1") (pintype "passive"))
      (node (ref "C13") (pin "1") (pinfunction "1_1") (pintype "passive"))
      (node (ref "C14") (pin "2") (pinfunction "2_2") (pintype "passive"))
      (node (ref "C15") (pin "1") (pinfunction "1_1") (pintype "passive"))
      (node (ref "D2") (pin "1") (pinfunction "1_1") (pintype "passive"))
      (node (ref "J4") (pin "6") (pinfunction "6_6") (pintype "passive"))
      (node (ref "R14") (pin "2") (pinfunction "2_2") (pintype "passive"))
      (node (ref "U3") (pin "19") (pinfunction "AVDD_19") (pintype "power_in"))
      (node (ref "U3") (pin "26") (pinfunction "VDD_26") (pintype "power_in"))
      (node (ref "U3") (pin "38") (pinfunction "VDD_38") (pintype "power_in"))
      (node (ref "U3") (pin "57") (pinfunction "VDD_57") (pintype "power_in"))
    )
    (net (code "81") (name "VDD_INT") (class "Default")
      (node (ref "D2") (pin "2") (pinfunction "2_2") (pintype "passive"))
      (node (ref "P1") (pin "5") (pinfunction "5_5") (pintype "passive"))
      (node (ref "P1") (pin "6") (pinfunction "6_6") (pintype "passive"))
      (node (ref "P1") (pin "7") (pinfunction "7_7") (pintype "passive"))
      (node (ref "P1") (pin "8") (pinfunction "8_8") (pintype "passive"))
      (node (ref "Q3") (pin "2") (pinfunction "S_2") (pintype "passive"))
      (node (ref "R15") (pin "1") (pinfunction "1_1") (pintype "passive"))
      (node (ref "R18") (pin "2") (pinfunction "2_2") (pintype "passive"))
      (node (ref "R23") (pin "1") (pinfunction "1_1") (pintype "passive"))
      (node (ref "R25") (pin "1") (pinfunction "1_1") (pintype "passive"))
      (node (ref "R26") (pin "2") (pinfunction "2_2") (pintype "passive"))
      (node (ref "R27") (pin "2") (pinfunction "2_2") (pintype "passive"))
      (node (ref "R29") (pin "1") (pinfunction "1_1") (pintype "passive"))
      (node (ref "R30") (pin "1") (pinfunction "1_1") (pintype "passive"))
      (node (ref "R31") (pin "2") (pinfunction "2_2") (pintype "passive"))
      (node (ref "R4") (pin "2") (pinfunction "2_2") (pintype "passive"))
      (node (ref "R5") (pin "1") (pinfunction "1_1") (pintype "passive"))
      (node (ref "R6") (pin "2") (pinfunction "2_2") (pintype "passive"))
    )
    (net (code "82") (name "unconnected-(J4-Pad1)") (class "Default")
      (node (ref "J4") (pin "1") (pinfunction "1_1") (pintype "passive"))
    )
    (net (code "83") (name "unconnected-(K1-Pad2)") (class "Default")
      (node (ref "K1") (pin "2") (pinfunction "2_2") (pintype "passive"))
    )
    (net (code "84") (name "unconnected-(TS1-Pad8)") (class "Default")
      (node (ref "TS1") (pin "8") (pinfunction "8_8") (pintype "passive"))
    )
    (net (code "85") (name "unconnected-(U2-INT1-Pad6)") (class "Default")
      (node (ref "U2") (pin "6") (pinfunction "INT1_6") (pintype "power_in+no_connect"))
    )
    (net (code "86") (name "unconnected-(U2-INT2-Pad5)") (class "Default")
      (node (ref "U2") (pin "5") (pinfunction "INT2_5") (pintype "power_in+no_connect"))
    )
    (net (code "87") (name "unconnected-(U3-RB0{slash}INT0{slash}FLT0-Pad48)") (class "Default")
      (node (ref "U3") (pin "48") (pinfunction "RB0/INT0/FLT0_48") (pintype "bidirectional+no_connect"))
    )
    (net (code "88") (name "unconnected-(U3-RC5{slash}SDO1-Pad36)") (class "Default")
      (node (ref "U3") (pin "36") (pinfunction "RC5/SDO1_36") (pintype "bidirectional+no_connect"))
    )
    (net (code "89") (name "unconnected-(U3-RD2{slash}PSP2-Pad54)") (class "Default")
      (node (ref "U3") (pin "54") (pinfunction "RD2/PSP2_54") (pintype "bidirectional+no_connect"))
    )
    (net (code "90") (name "unconnected-(U3-RD7{slash}PSP7{slash}~{SS2}-Pad49)") (class "Default")
      (node (ref "U3") (pin "49") (pinfunction "RD7/PSP7/~{SS2}_49") (pintype "bidirectional+no_connect"))
    )
    (net (code "91") (name "unconnected-(U3-RE0{slash}~{RD}{slash}P2D-Pad2)") (class "Default")
      (node (ref "U3") (pin "2") (pinfunction "RE0/~{RD}/P2D_2") (pintype "bidirectional+no_connect"))
    )
    (net (code "92") (name "unconnected-(U3-RE1{slash}~{WR}{slash}P2C-Pad1)") (class "Default")
      (node (ref "U3") (pin "1") (pinfunction "RE1/~{WR}/P2C_1") (pintype "bidirectional+no_connect"))
    )
    (net (code "93") (name "unconnected-(U3-RE2{slash}~{CS}{slash}P2B-Pad64)") (class "Default")
      (node (ref "U3") (pin "64") (pinfunction "RE2/~{CS}/P2B_64") (pintype "bidirectional+no_connect"))
    )
    (net (code "94") (name "unconnected-(U3-RE6{slash}P1B-Pad60)") (class "Default")
      (node (ref "U3") (pin "60") (pinfunction "RE6/P1B_60") (pintype "bidirectional+no_connect"))
    )
    (net (code "95") (name "unconnected-(U3-RE7{slash}ECCP2{slash}P2A-Pad59)") (class "Default")
      (node (ref "U3") (pin "59") (pinfunction "RE7/ECCP2/P2A_59") (pintype "bidirectional+no_connect"))
    )
    (net (code "96") (name "unconnected-(U3-RF3{slash}AN8-Pad15)") (class "Default")
      (node (ref "U3") (pin "15") (pinfunction "RF3/AN8_15") (pintype "bidirectional+no_connect"))
    )
    (net (code "97") (name "unconnected-(U3-RF4{slash}AN9-Pad14)") (class "Default")
      (node (ref "U3") (pin "14") (pinfunction "RF4/AN9_14") (pintype "bidirectional+no_connect"))
    )
    (net (code "98") (name "unconnected-(U3-RG0{slash}ECCP3{slash}P3A-Pad3)") (class "Default")
      (node (ref "U3") (pin "3") (pinfunction "RG0/ECCP3/P3A_3") (pintype "bidirectional+no_connect"))
    )
    (net (code "99") (name "unconnected-(U3-RG1{slash}TX2{slash}CK2-Pad4)") (class "Default")
      (node (ref "U3") (pin "4") (pinfunction "RG1/TX2/CK2_4") (pintype "bidirectional+no_connect"))
    )
    (net (code "100") (name "unconnected-(U3-RG2{slash}RX2{slash}DT2-Pad5)") (class "Default")
      (node (ref "U3") (pin "5") (pinfunction "RG2/RX2/DT2_5") (pintype "bidirectional+no_connect"))
    )
    (net (code "101") (name "unconnected-(U9-DG-Pad3)") (class "Default")
      (node (ref "U9") (pin "3") (pinfunction "DG_3") (pintype "passive+no_connect"))
    )
  )
)
